# nRF52833_MCU.net
KiCad netlist of a schematic drawn in EAGLE
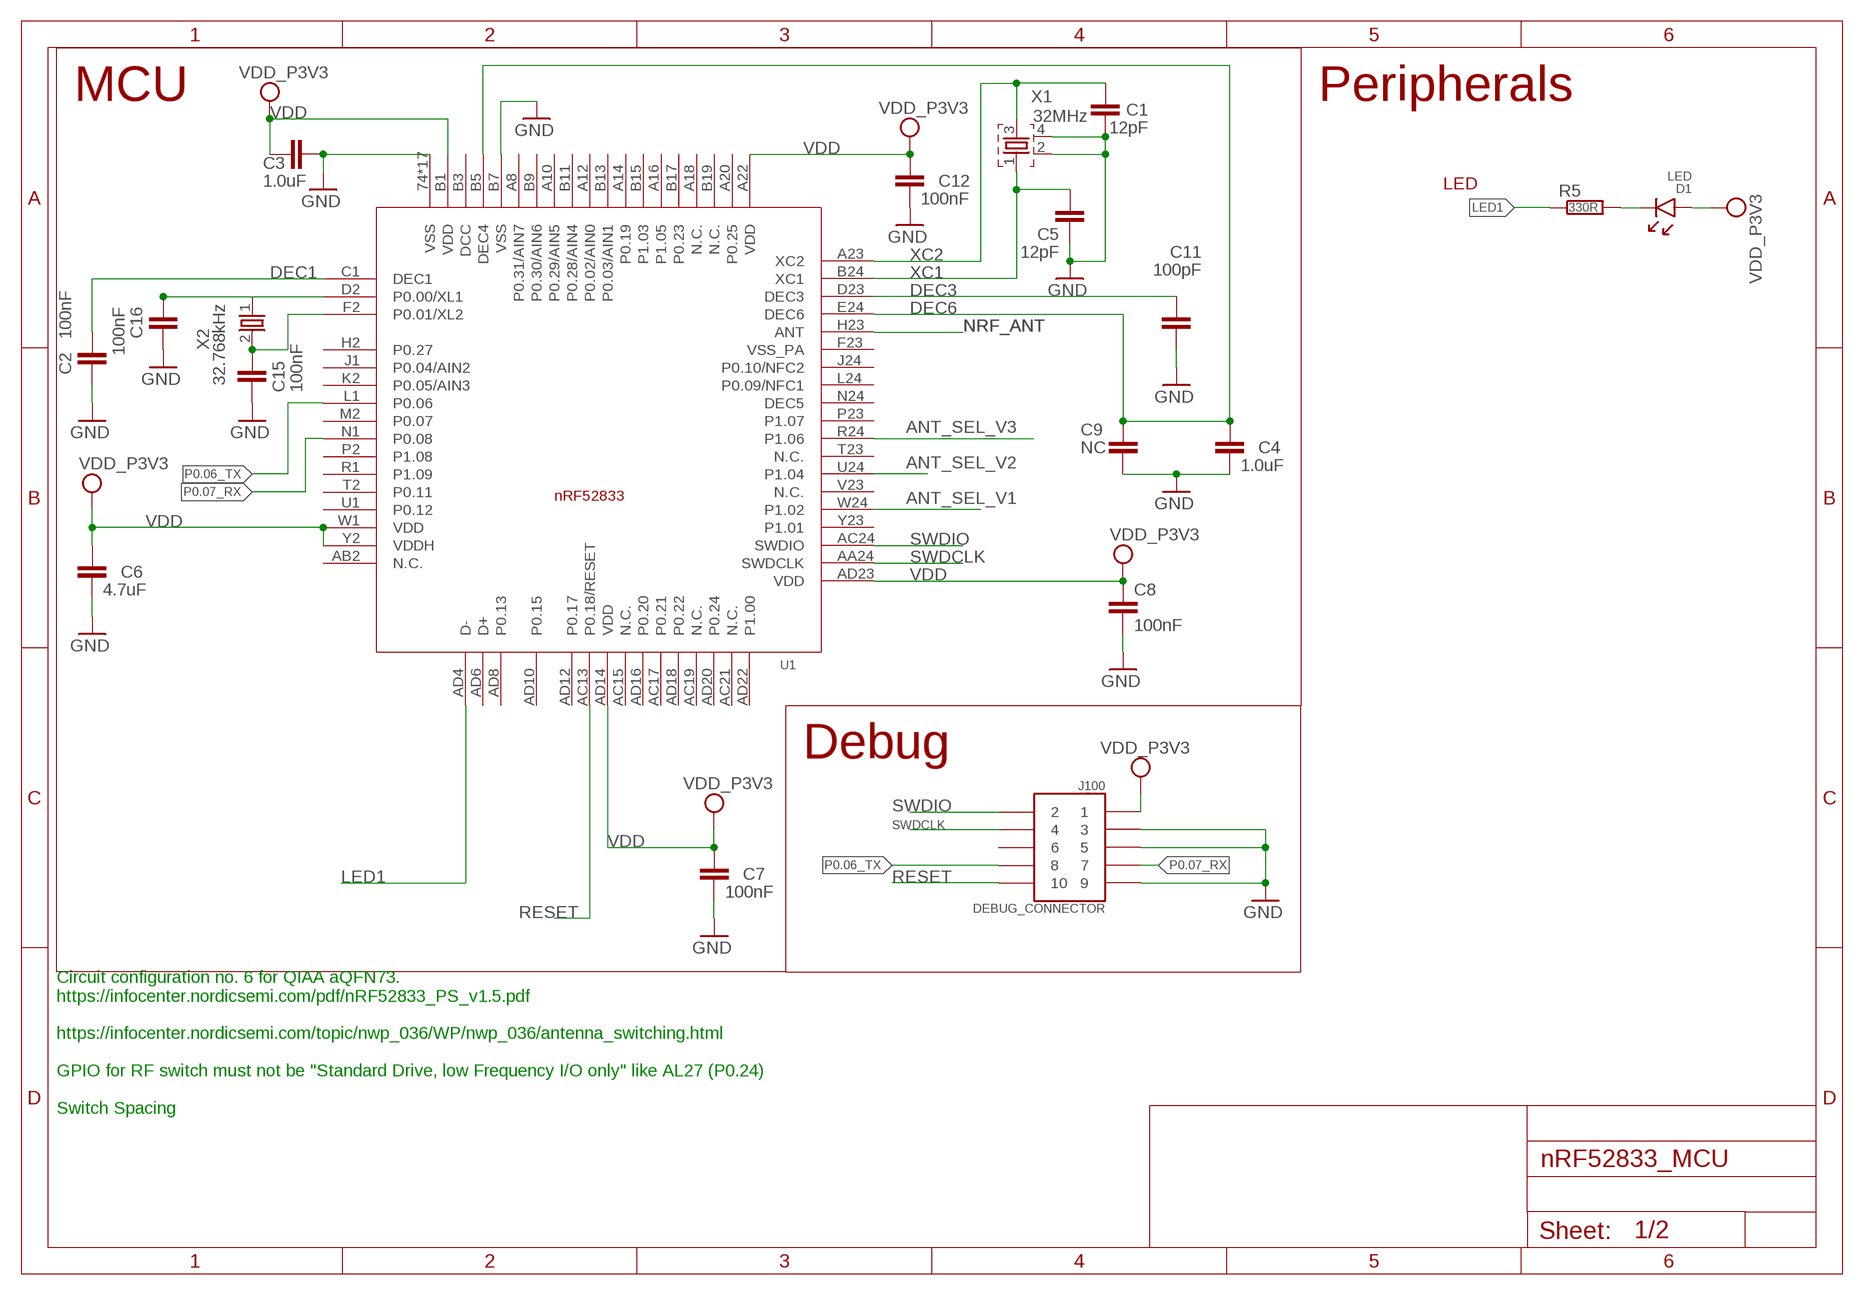
[diagram p0: schematic, sheet 1]
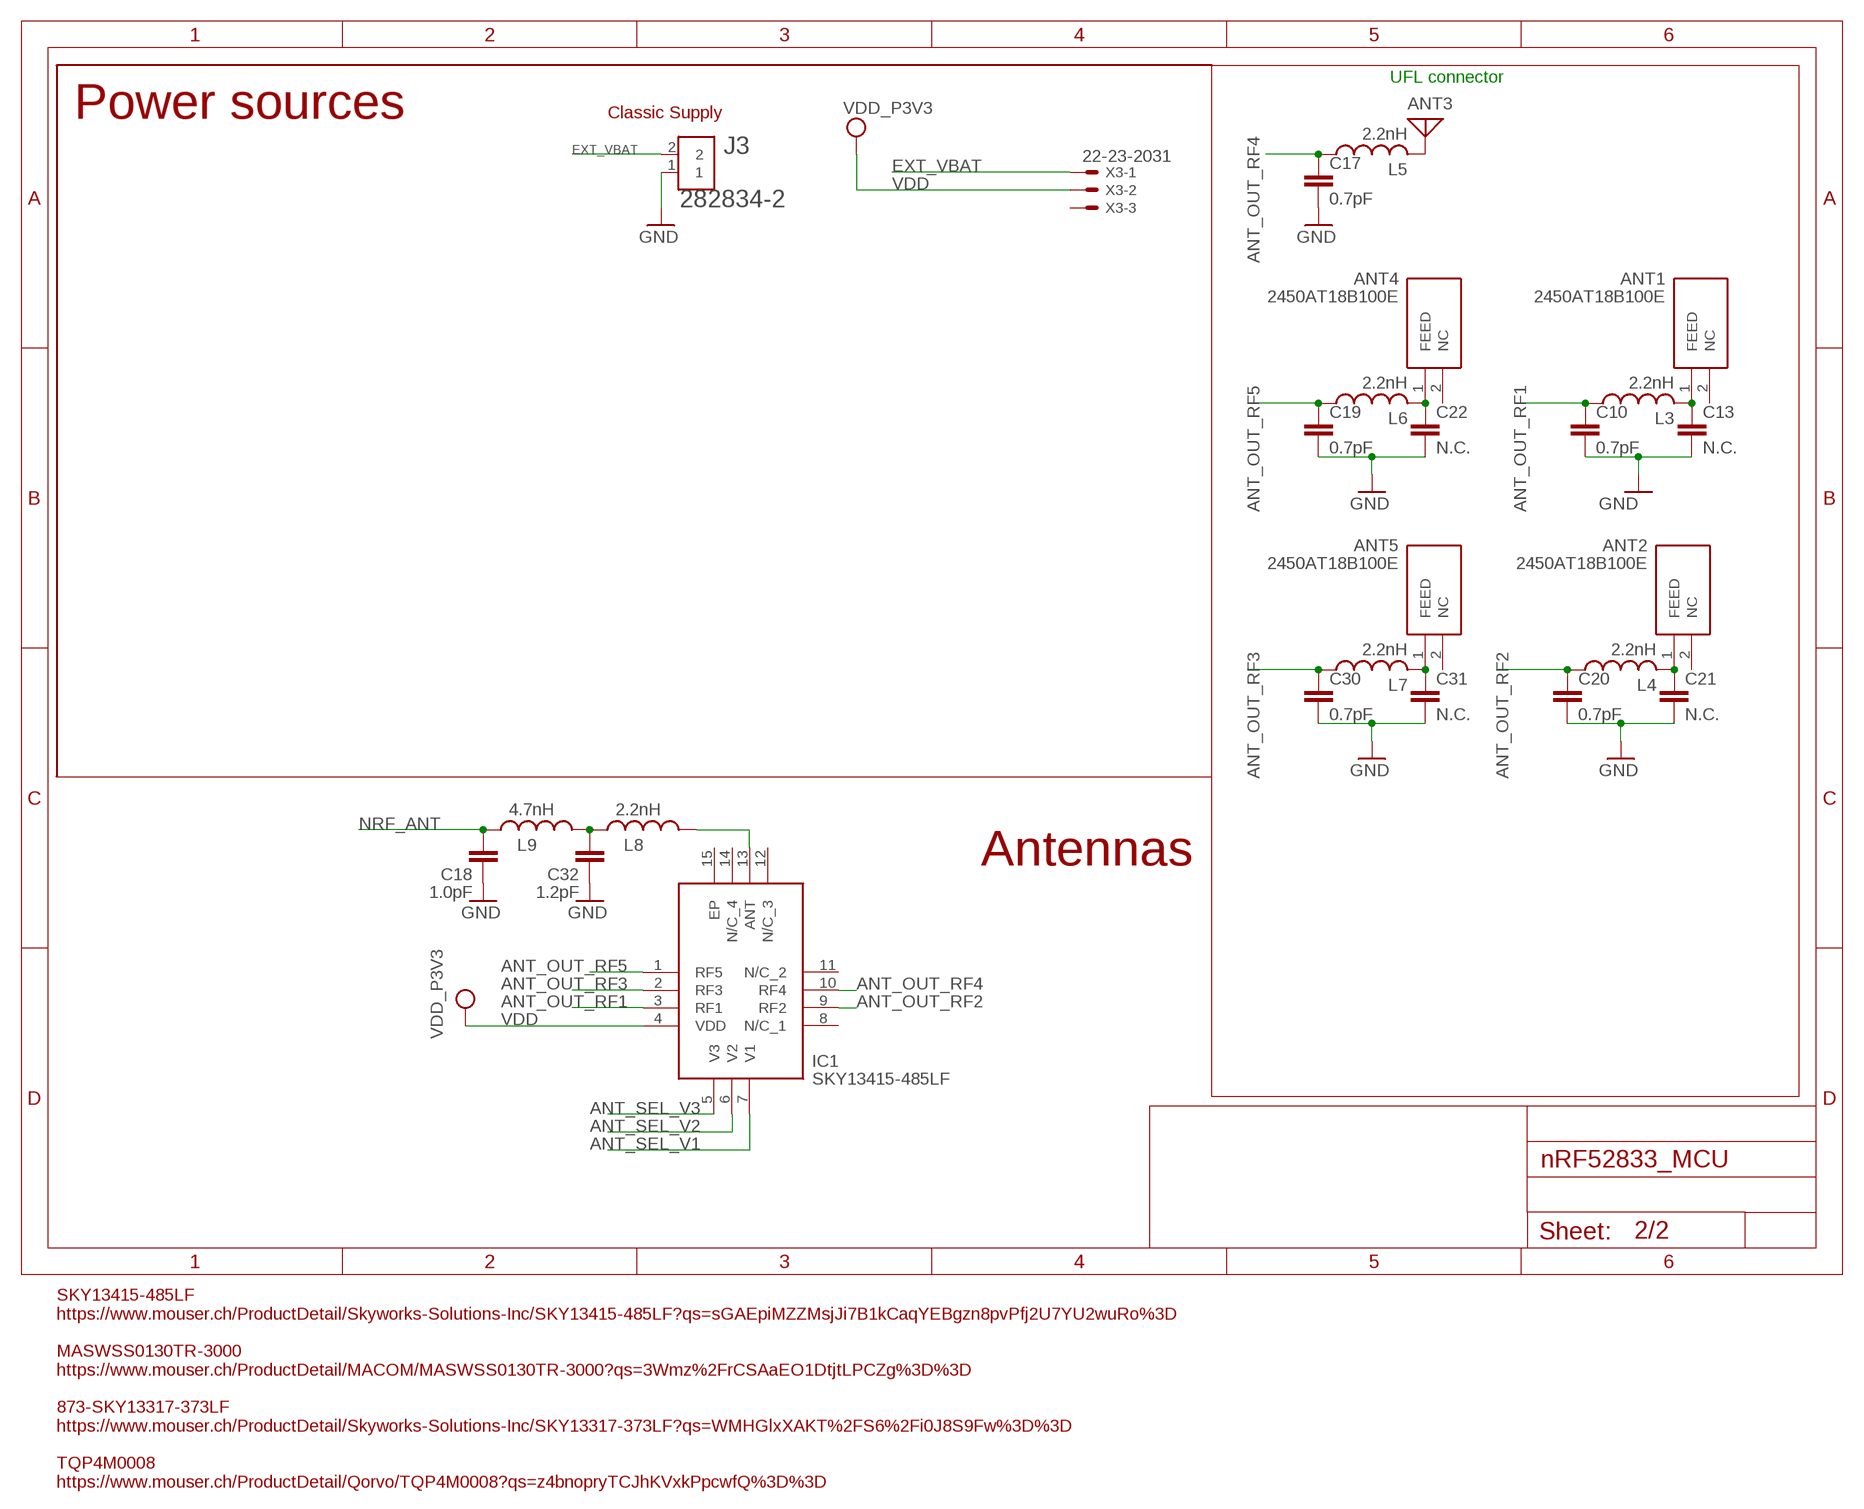
[diagram p1: schematic, sheet 2]

(export (version "E")
  (design (tool "Eeschema 10.0.6"))
  (components
    (comp (ref "ANT1")
      (value "2450AT18B100E")
      (footprint "eagle-import:ANTC3216X140N")
      (fields (field (name "MOUSER_PART_NUMBER") "609-2450AT18B100E"))
      (libsource (lib "eagle-import") (part "2450AT18B100E"))
    )
    (comp (ref "ANT2")
      (value "2450AT18B100E")
      (footprint "eagle-import:ANTC3216X140N")
      (fields (field (name "MOUSER_PART_NUMBER") "609-2450AT18B100E"))
      (libsource (lib "eagle-import") (part "2450AT18B100E"))
    )
    (comp (ref "ANT3")
      (value "ANTENNA")
      (footprint "eagle-import:PAD-01")
      (libsource (lib "eagle-import") (part "ANTENNA"))
    )
    (comp (ref "ANT4")
      (value "2450AT18B100E")
      (footprint "eagle-import:ANTC3216X140N")
      (fields (field (name "MOUSER_PART_NUMBER") "609-2450AT18B100E"))
      (libsource (lib "eagle-import") (part "2450AT18B100E"))
    )
    (comp (ref "ANT5")
      (value "2450AT18B100E")
      (footprint "eagle-import:ANTC3216X140N")
      (fields (field (name "MOUSER_PART_NUMBER") "609-2450AT18B100E"))
      (libsource (lib "eagle-import") (part "2450AT18B100E"))
    )
    (comp (ref "C10")
      (value "0.7pF")
      (footprint "eagle-import:RESC0402_N")
      (libsource (lib "eagle-import") (part "CAPACITOR_0402_N"))
    )
    (comp (ref "C13")
      (value "N.C.")
      (footprint "eagle-import:RESC0402_N")
      (libsource (lib "eagle-import") (part "CAPACITOR_0402_N"))
    )
    (comp (ref "C17")
      (value "0.7pF")
      (footprint "eagle-import:RESC0402_N")
      (libsource (lib "eagle-import") (part "CAPACITOR_0402_N"))
    )
    (comp (ref "C18")
      (value "1.0pF")
      (footprint "eagle-import:RESC0402_N")
      (libsource (lib "eagle-import") (part "CAPACITOR_0402_N"))
    )
    (comp (ref "C19")
      (value "0.7pF")
      (footprint "eagle-import:RESC0402_N")
      (libsource (lib "eagle-import") (part "CAPACITOR_0402_N"))
    )
    (comp (ref "C20")
      (value "0.7pF")
      (footprint "eagle-import:RESC0402_N")
      (libsource (lib "eagle-import") (part "CAPACITOR_0402_N"))
    )
    (comp (ref "C21")
      (value "N.C.")
      (footprint "eagle-import:RESC0402_N")
      (libsource (lib "eagle-import") (part "CAPACITOR_0402_N"))
    )
    (comp (ref "C22")
      (value "N.C.")
      (footprint "eagle-import:RESC0402_N")
      (libsource (lib "eagle-import") (part "CAPACITOR_0402_N"))
    )
    (comp (ref "C30")
      (value "0.7pF")
      (footprint "eagle-import:RESC0402_N")
      (libsource (lib "eagle-import") (part "CAPACITOR_0402_N"))
    )
    (comp (ref "C31")
      (value "N.C.")
      (footprint "eagle-import:RESC0402_N")
      (libsource (lib "eagle-import") (part "CAPACITOR_0402_N"))
    )
    (comp (ref "C32")
      (value "1.2pF")
      (footprint "eagle-import:RESC0402_N")
      (libsource (lib "eagle-import") (part "CAPACITOR_0402_N"))
    )
    (comp (ref "IC1")
      (value "SKY13415-485LF")
      (footprint "eagle-import:SKY13415485LF")
      (fields (field (name "MOUSER_PART_NUMBER") "873-SKY13415-485LF"))
      (libsource (lib "eagle-import") (part "SKY13415-485LF"))
    )
    (comp (ref "J3")
      (value "282834-2")
      (footprint "eagle-import:CONN_282834-2")
      (fields (field (name "MF") "TE Connectivity"))
      (libsource (lib "eagle-import") (part "282834-2"))
    )
    (comp (ref "L3")
      (value "2.2nH")
      (footprint "eagle-import:RESC0402_N")
      (libsource (lib "eagle-import") (part "INDUCTOR_0402_N"))
    )
    (comp (ref "L4")
      (value "2.2nH")
      (footprint "eagle-import:RESC0402_N")
      (libsource (lib "eagle-import") (part "INDUCTOR_0402_N"))
    )
    (comp (ref "L5")
      (value "2.2nH")
      (footprint "eagle-import:RESC0402_N")
      (libsource (lib "eagle-import") (part "INDUCTOR_0402_N"))
    )
    (comp (ref "L6")
      (value "2.2nH")
      (footprint "eagle-import:RESC0402_N")
      (libsource (lib "eagle-import") (part "INDUCTOR_0402_N"))
    )
    (comp (ref "L7")
      (value "2.2nH")
      (footprint "eagle-import:RESC0402_N")
      (libsource (lib "eagle-import") (part "INDUCTOR_0402_N"))
    )
    (comp (ref "L8")
      (value "2.2nH")
      (footprint "eagle-import:RESC0402_N")
      (libsource (lib "eagle-import") (part "INDUCTOR_0402_N"))
    )
    (comp (ref "L9")
      (value "4.7nH")
      (footprint "eagle-import:RESC0402_N")
      (libsource (lib "eagle-import") (part "INDUCTOR_0402_N"))
    )
    (comp (ref "X3")
      (value "22-23-2031")
      (footprint "eagle-import:22-23-2031")
      (fields (field (name "MF") "MOLEX"))
      (libsource (lib "eagle-import") (part "22-23-2031"))
    )
    (comp (ref "C1")
      (value "12pF")
      (footprint "eagle-import:RESC0402_N")
      (libsource (lib "eagle-import") (part "CAPACITOR_0402_N"))
    )
    (comp (ref "C2")
      (value "100nF")
      (footprint "eagle-import:RESC0402_N")
      (libsource (lib "eagle-import") (part "CAPACITOR_0402_N"))
    )
    (comp (ref "C3")
      (value "1.0uF")
      (footprint "eagle-import:RESC0402_N")
      (libsource (lib "eagle-import") (part "CAPACITOR_0402_N"))
    )
    (comp (ref "C4")
      (value "1.0uF")
      (footprint "eagle-import:RESC0402_N")
      (libsource (lib "eagle-import") (part "CAPACITOR_0402_N"))
    )
    (comp (ref "C5")
      (value "12pF")
      (footprint "eagle-import:RESC0402_N")
      (libsource (lib "eagle-import") (part "CAPACITOR_0402_N"))
    )
    (comp (ref "C6")
      (value "4.7uF")
      (footprint "eagle-import:RESC0402_N")
      (libsource (lib "eagle-import") (part "CAPACITOR_0402_N"))
    )
    (comp (ref "C7")
      (value "100nF")
      (footprint "eagle-import:RESC0402_N")
      (libsource (lib "eagle-import") (part "CAPACITOR_0402_N"))
    )
    (comp (ref "C8")
      (value "100nF")
      (footprint "eagle-import:RESC0402_N")
      (libsource (lib "eagle-import") (part "CAPACITOR_0402_N"))
    )
    (comp (ref "C9")
      (value "NC")
      (footprint "eagle-import:RESC0402_N")
      (libsource (lib "eagle-import") (part "CAPACITOR_0402_N"))
    )
    (comp (ref "C11")
      (value "100pF")
      (footprint "eagle-import:RESC0402_N")
      (libsource (lib "eagle-import") (part "CAPACITOR_0402_N"))
    )
    (comp (ref "C12")
      (value "100nF")
      (footprint "eagle-import:RESC0402_N")
      (libsource (lib "eagle-import") (part "CAPACITOR_0402_N"))
    )
    (comp (ref "C15")
      (value "100nF")
      (footprint "eagle-import:RESC0402_N")
      (libsource (lib "eagle-import") (part "CAPACITOR_0402_N"))
    )
    (comp (ref "C16")
      (value "100nF")
      (footprint "eagle-import:RESC0402_N")
      (libsource (lib "eagle-import") (part "CAPACITOR_0402_N"))
    )
    (comp (ref "D1")
      (value "LED")
      (footprint "eagle-import:DIOC0603_N")
      (libsource (lib "eagle-import") (part "LED"))
    )
    (comp (ref "J100")
      (value "DEBUG_CONNECTOR")
      (footprint "eagle-import:HDRV127P5X2-10_N")
      (libsource (lib "eagle-import") (part "DEBUG_CONNECTOR"))
    )
    (comp (ref "R5")
      (value "330R")
      (footprint "eagle-import:RESC0402_N")
      (libsource (lib "eagle-import") (part "RESISTOR_0402_N"))
    )
    (comp (ref "U1")
      (value "nRF52833-QIAA")
      (footprint "eagle-import:AQFN50P700X700X85_HS-74N")
      (fields
        (field (name "MANUFACTURER") "Nordic Semiconductor")
        (field (name "PUBLISHER") "Nordic Semiconductor")
      )
      (libsource (lib "eagle-import") (part "NRF52833_QIAANRF52833_QIAA_AQFN50P700X700X85_HS-74N"))
    )
    (comp (ref "X1")
      (value "32MHz")
      (footprint "eagle-import:BT-XTAL_2016_N")
      (libsource (lib "eagle-import") (part "XTAL_32MHZ"))
    )
    (comp (ref "X2")
      (value "32.768kHz")
      (footprint "eagle-import:XTAL_3215_N")
      (libsource (lib "eagle-import") (part "XTAL_32KHZ"))
    )
  )
  (nets
    (net (code "1") (name "ANT_OUT_RF1") (class "Default")
      (node (ref "C10") (pin "1") (pinfunction "1_1") (pintype "passive"))
      (node (ref "IC1") (pin "3") (pinfunction "RF1_3") (pintype "bidirectional"))
      (node (ref "L3") (pin "1") (pinfunction "1_1") (pintype "passive"))
    )
    (net (code "2") (name "ANT_OUT_RF2") (class "Default")
      (node (ref "C20") (pin "1") (pinfunction "1_1") (pintype "passive"))
      (node (ref "IC1") (pin "9") (pinfunction "RF2_9") (pintype "bidirectional"))
      (node (ref "L4") (pin "1") (pinfunction "1_1") (pintype "passive"))
    )
    (net (code "3") (name "ANT_OUT_RF3") (class "Default")
      (node (ref "C30") (pin "1") (pinfunction "1_1") (pintype "passive"))
      (node (ref "IC1") (pin "2") (pinfunction "RF3_2") (pintype "bidirectional"))
      (node (ref "L7") (pin "1") (pinfunction "1_1") (pintype "passive"))
    )
    (net (code "4") (name "ANT_OUT_RF4") (class "Default")
      (node (ref "C17") (pin "1") (pinfunction "1_1") (pintype "passive"))
      (node (ref "IC1") (pin "10") (pinfunction "RF4_10") (pintype "bidirectional"))
      (node (ref "L5") (pin "1") (pinfunction "1_1") (pintype "passive"))
    )
    (net (code "5") (name "ANT_OUT_RF5") (class "Default")
      (node (ref "C19") (pin "1") (pinfunction "1_1") (pintype "passive"))
      (node (ref "IC1") (pin "1") (pinfunction "RF5_1") (pintype "bidirectional"))
      (node (ref "L6") (pin "1") (pinfunction "1_1") (pintype "passive"))
    )
    (net (code "6") (name "ANT_SEL_V1") (class "Default")
      (node (ref "IC1") (pin "7") (pinfunction "V1_7") (pintype "bidirectional"))
      (node (ref "U1") (pin "W24") (pinfunction "P1.02_W24") (pintype "bidirectional"))
    )
    (net (code "7") (name "ANT_SEL_V2") (class "Default")
      (node (ref "IC1") (pin "6") (pinfunction "V2_6") (pintype "bidirectional"))
      (node (ref "U1") (pin "U24") (pinfunction "P1.04_U24") (pintype "bidirectional"))
    )
    (net (code "8") (name "ANT_SEL_V3") (class "Default")
      (node (ref "IC1") (pin "5") (pinfunction "V3_5") (pintype "bidirectional"))
      (node (ref "U1") (pin "R24") (pinfunction "P1.06_R24") (pintype "bidirectional"))
    )
    (net (code "9") (name "DEC1") (class "Default")
      (node (ref "C2") (pin "1") (pinfunction "1_1") (pintype "passive"))
      (node (ref "U1") (pin "C1") (pinfunction "DEC1_C1") (pintype "power_in"))
    )
    (net (code "10") (name "DEC3") (class "Default")
      (node (ref "C11") (pin "1") (pinfunction "1_1") (pintype "passive"))
      (node (ref "U1") (pin "D23") (pinfunction "DEC3_D23") (pintype "power_in"))
    )
    (net (code "11") (name "DEC5") (class "Default")
      (node (ref "U1") (pin "N24") (pinfunction "DEC5_N24") (pintype "power_in"))
    )
    (net (code "12") (name "DEC6") (class "Default")
      (node (ref "C4") (pin "1") (pinfunction "1_1") (pintype "passive"))
      (node (ref "C9") (pin "1") (pinfunction "1_1") (pintype "passive"))
      (node (ref "U1") (pin "B5") (pinfunction "DEC4_B5") (pintype "power_in"))
      (node (ref "U1") (pin "E24") (pinfunction "DEC6_E24") (pintype "power_in"))
    )
    (net (code "13") (name "EXT_VBAT") (class "Default")
      (node (ref "J3") (pin "2") (pinfunction "2_2") (pintype "passive"))
      (node (ref "X3") (pin "1") (pinfunction "S_1") (pintype "passive"))
    )
    (net (code "14") (name "GND") (class "Default")
      (node (ref "C1") (pin "2") (pinfunction "2_2") (pintype "passive"))
      (node (ref "C10") (pin "2") (pinfunction "2_2") (pintype "passive"))
      (node (ref "C11") (pin "2") (pinfunction "2_2") (pintype "passive"))
      (node (ref "C12") (pin "2") (pinfunction "2_2") (pintype "passive"))
      (node (ref "C13") (pin "2") (pinfunction "2_2") (pintype "passive"))
      (node (ref "C15") (pin "1") (pinfunction "1_1") (pintype "passive"))
      (node (ref "C16") (pin "1") (pinfunction "1_1") (pintype "passive"))
      (node (ref "C17") (pin "2") (pinfunction "2_2") (pintype "passive"))
      (node (ref "C18") (pin "2") (pinfunction "2_2") (pintype "passive"))
      (node (ref "C19") (pin "2") (pinfunction "2_2") (pintype "passive"))
      (node (ref "C2") (pin "2") (pinfunction "2_2") (pintype "passive"))
      (node (ref "C20") (pin "2") (pinfunction "2_2") (pintype "passive"))
      (node (ref "C21") (pin "2") (pinfunction "2_2") (pintype "passive"))
      (node (ref "C22") (pin "2") (pinfunction "2_2") (pintype "passive"))
      (node (ref "C3") (pin "2") (pinfunction "2_2") (pintype "passive"))
      (node (ref "C30") (pin "2") (pinfunction "2_2") (pintype "passive"))
      (node (ref "C31") (pin "2") (pinfunction "2_2") (pintype "passive"))
      (node (ref "C32") (pin "2") (pinfunction "2_2") (pintype "passive"))
      (node (ref "C4") (pin "2") (pinfunction "2_2") (pintype "passive"))
      (node (ref "C5") (pin "2") (pinfunction "2_2") (pintype "passive"))
      (node (ref "C6") (pin "2") (pinfunction "2_2") (pintype "passive"))
      (node (ref "C7") (pin "2") (pinfunction "2_2") (pintype "passive"))
      (node (ref "C8") (pin "2") (pinfunction "2_2") (pintype "passive"))
      (node (ref "C9") (pin "2") (pinfunction "2_2") (pintype "passive"))
      (node (ref "J100") (pin "3") (pinfunction "3_3") (pintype "bidirectional"))
      (node (ref "J100") (pin "5") (pinfunction "5_5") (pintype "bidirectional"))
      (node (ref "J100") (pin "9") (pinfunction "9_9") (pintype "bidirectional"))
      (node (ref "J3") (pin "1") (pinfunction "1_1") (pintype "passive"))
      (node (ref "U1") (pin "74") (pinfunction "VSS_74") (pintype "power_in"))
      (node (ref "U1") (pin "B7") (pinfunction "VSS_B7") (pintype "power_in"))
      (node (ref "U1") (pin "P$1") (pinfunction "VSS_P$1") (pintype "power_in"))
      (node (ref "U1") (pin "P$10") (pinfunction "VSS_P$10") (pintype "power_in"))
      (node (ref "U1") (pin "P$11") (pinfunction "VSS_P$11") (pintype "power_in"))
      (node (ref "U1") (pin "P$12") (pinfunction "VSS_P$12") (pintype "power_in"))
      (node (ref "U1") (pin "P$13") (pinfunction "VSS_P$13") (pintype "power_in"))
      (node (ref "U1") (pin "P$14") (pinfunction "VSS_P$14") (pintype "power_in"))
      (node (ref "U1") (pin "P$15") (pinfunction "VSS_P$15") (pintype "power_in"))
      (node (ref "U1") (pin "P$16") (pinfunction "VSS_P$16") (pintype "power_in"))
      (node (ref "U1") (pin "P$17") (pinfunction "VSS_P$17") (pintype "power_in"))
      (node (ref "U1") (pin "P$18") (pinfunction "VSS_P$18") (pintype "power_in"))
      (node (ref "U1") (pin "P$19") (pinfunction "VSS_P$19") (pintype "power_in"))
      (node (ref "U1") (pin "P$2") (pinfunction "VSS_P$2") (pintype "power_in"))
      (node (ref "U1") (pin "P$20") (pinfunction "VSS_P$20") (pintype "power_in"))
      (node (ref "U1") (pin "P$3") (pinfunction "VSS_P$3") (pintype "power_in"))
      (node (ref "U1") (pin "P$4") (pinfunction "VSS_P$4") (pintype "power_in"))
      (node (ref "U1") (pin "P$5") (pinfunction "VSS_P$5") (pintype "power_in"))
      (node (ref "X1") (pin "2") (pinfunction "2_2") (pintype "passive"))
      (node (ref "X1") (pin "4") (pinfunction "4_4") (pintype "passive"))
    )
    (net (code "15") (name "LED1") (class "Default")
      (node (ref "R5") (pin "1") (pinfunction "1_1") (pintype "passive"))
      (node (ref "U1") (pin "AD4") (pinfunction "D-_AD4") (pintype "bidirectional"))
    )
    (net (code "16") (name "NRF_ANT") (class "Default")
      (node (ref "C18") (pin "1") (pinfunction "1_1") (pintype "passive"))
      (node (ref "L9") (pin "1") (pinfunction "1_1") (pintype "passive"))
      (node (ref "U1") (pin "H23") (pinfunction "ANT_H23") (pintype "bidirectional"))
    )
    (net (code "17") (name "Net-(ANT1-FEED)") (class "Default")
      (node (ref "ANT1") (pin "1") (pinfunction "FEED_1") (pintype "input"))
      (node (ref "C13") (pin "1") (pinfunction "1_1") (pintype "passive"))
      (node (ref "L3") (pin "2") (pinfunction "2_2") (pintype "passive"))
    )
    (net (code "18") (name "Net-(ANT2-FEED)") (class "Default")
      (node (ref "ANT2") (pin "1") (pinfunction "FEED_1") (pintype "input"))
      (node (ref "C21") (pin "1") (pinfunction "1_1") (pintype "passive"))
      (node (ref "L4") (pin "2") (pinfunction "2_2") (pintype "passive"))
    )
    (net (code "19") (name "Net-(ANT3-Pad1)") (class "Default")
      (node (ref "ANT3") (pin "1") (pinfunction "1_1") (pintype "output"))
      (node (ref "L5") (pin "2") (pinfunction "2_2") (pintype "passive"))
    )
    (net (code "20") (name "Net-(ANT4-FEED)") (class "Default")
      (node (ref "ANT4") (pin "1") (pinfunction "FEED_1") (pintype "input"))
      (node (ref "C22") (pin "1") (pinfunction "1_1") (pintype "passive"))
      (node (ref "L6") (pin "2") (pinfunction "2_2") (pintype "passive"))
    )
    (net (code "21") (name "Net-(ANT5-FEED)") (class "Default")
      (node (ref "ANT5") (pin "1") (pinfunction "FEED_1") (pintype "input"))
      (node (ref "C31") (pin "1") (pinfunction "1_1") (pintype "passive"))
      (node (ref "L7") (pin "2") (pinfunction "2_2") (pintype "passive"))
    )
    (net (code "22") (name "Net-(C32-Pad1)") (class "Default")
      (node (ref "C32") (pin "1") (pinfunction "1_1") (pintype "passive"))
      (node (ref "L8") (pin "1") (pinfunction "1_1") (pintype "passive"))
      (node (ref "L9") (pin "2") (pinfunction "2_2") (pintype "passive"))
    )
    (net (code "23") (name "Net-(D1-C)") (class "Default")
      (node (ref "D1") (pin "1") (pinfunction "C_1") (pintype "bidirectional"))
      (node (ref "R5") (pin "2") (pinfunction "2_2") (pintype "passive"))
    )
    (net (code "24") (name "Net-(IC1-ANT)") (class "Default")
      (node (ref "IC1") (pin "13") (pinfunction "ANT_13") (pintype "bidirectional"))
      (node (ref "L8") (pin "2") (pinfunction "2_2") (pintype "passive"))
    )
    (net (code "25") (name "Net-(U1-P0.00{slash}XL1)") (class "Default")
      (node (ref "C16") (pin "2") (pinfunction "2_2") (pintype "passive"))
      (node (ref "U1") (pin "D2") (pinfunction "P0.00/XL1_D2") (pintype "bidirectional"))
      (node (ref "X2") (pin "1") (pinfunction "1_1") (pintype "passive"))
    )
    (net (code "26") (name "Net-(U1-P0.01{slash}XL2)") (class "Default")
      (node (ref "C15") (pin "2") (pinfunction "2_2") (pintype "passive"))
      (node (ref "U1") (pin "F2") (pinfunction "P0.01/XL2_F2") (pintype "bidirectional"))
      (node (ref "X2") (pin "2") (pinfunction "2_2") (pintype "passive"))
    )
    (net (code "27") (name "P0.06_TX") (class "Default")
      (node (ref "J100") (pin "8") (pinfunction "8_8") (pintype "bidirectional"))
      (node (ref "U1") (pin "L1") (pinfunction "P0.06_L1") (pintype "bidirectional"))
    )
    (net (code "28") (name "P0.07_RX") (class "Default")
      (node (ref "J100") (pin "7") (pinfunction "7_7") (pintype "bidirectional"))
      (node (ref "U1") (pin "N1") (pinfunction "P0.08_N1") (pintype "bidirectional"))
    )
    (net (code "29") (name "RESET") (class "Default")
      (node (ref "J100") (pin "10") (pinfunction "10_10") (pintype "bidirectional"))
      (node (ref "U1") (pin "AC13") (pinfunction "P0.18/RESET_AC13") (pintype "bidirectional"))
    )
    (net (code "30") (name "SWDCLK") (class "Default")
      (node (ref "J100") (pin "4") (pinfunction "4_4") (pintype "bidirectional"))
      (node (ref "U1") (pin "AA24") (pinfunction "SWDCLK_AA24") (pintype "input"))
    )
    (net (code "31") (name "SWDIO") (class "Default")
      (node (ref "J100") (pin "2") (pinfunction "2_2") (pintype "bidirectional"))
      (node (ref "U1") (pin "AC24") (pinfunction "SWDIO_AC24") (pintype "bidirectional"))
    )
    (net (code "32") (name "VDD") (class "Default")
      (node (ref "C12") (pin "1") (pinfunction "1_1") (pintype "passive"))
      (node (ref "C3") (pin "1") (pinfunction "1_1") (pintype "passive"))
      (node (ref "C6") (pin "1") (pinfunction "1_1") (pintype "passive"))
      (node (ref "C7") (pin "1") (pinfunction "1_1") (pintype "passive"))
      (node (ref "C8") (pin "1") (pinfunction "1_1") (pintype "passive"))
      (node (ref "D1") (pin "2") (pinfunction "A_2") (pintype "bidirectional"))
      (node (ref "IC1") (pin "4") (pinfunction "VDD_4") (pintype "bidirectional"))
      (node (ref "J100") (pin "1") (pinfunction "1_1") (pintype "bidirectional"))
      (node (ref "U1") (pin "A22") (pinfunction "VDD_A22") (pintype "power_in"))
      (node (ref "U1") (pin "AD14") (pinfunction "VDD_AD14") (pintype "power_in"))
      (node (ref "U1") (pin "AD23") (pinfunction "VDD_AD23") (pintype "power_in"))
      (node (ref "U1") (pin "B1") (pinfunction "VDD_B1") (pintype "power_in"))
      (node (ref "U1") (pin "W1") (pinfunction "VDD_W1") (pintype "power_in"))
      (node (ref "U1") (pin "Y2") (pinfunction "VDDH_Y2") (pintype "power_in"))
      (node (ref "X3") (pin "2") (pinfunction "S_2") (pintype "passive"))
    )
    (net (code "33") (name "VSS_PA") (class "Default")
      (node (ref "U1") (pin "F23") (pinfunction "VSS_PA_F23") (pintype "power_in"))
    )
    (net (code "34") (name "XC1") (class "Default")
      (node (ref "C5") (pin "1") (pinfunction "1_1") (pintype "passive"))
      (node (ref "U1") (pin "B24") (pinfunction "XC1_B24") (pintype "input"))
      (node (ref "X1") (pin "1") (pinfunction "1_1") (pintype "passive"))
    )
    (net (code "35") (name "XC2") (class "Default")
      (node (ref "C1") (pin "1") (pinfunction "1_1") (pintype "passive"))
      (node (ref "U1") (pin "A23") (pinfunction "XC2_A23") (pintype "output"))
      (node (ref "X1") (pin "3") (pinfunction "3_3") (pintype "passive"))
    )
    (net (code "36") (name "unconnected-(ANT1-NC-Pad2)") (class "Default")
      (node (ref "ANT1") (pin "2") (pinfunction "NC_2") (pintype "no_connect"))
    )
    (net (code "37") (name "unconnected-(ANT2-NC-Pad2)") (class "Default")
      (node (ref "ANT2") (pin "2") (pinfunction "NC_2") (pintype "no_connect"))
    )
    (net (code "38") (name "unconnected-(ANT4-NC-Pad2)") (class "Default")
      (node (ref "ANT4") (pin "2") (pinfunction "NC_2") (pintype "no_connect"))
    )
    (net (code "39") (name "unconnected-(ANT5-NC-Pad2)") (class "Default")
      (node (ref "ANT5") (pin "2") (pinfunction "NC_2") (pintype "no_connect"))
    )
    (net (code "40") (name "unconnected-(IC1-EP-Pad15)") (class "Default")
      (node (ref "IC1") (pin "15") (pinfunction "EP_15") (pintype "bidirectional"))
    )
    (net (code "41") (name "unconnected-(IC1-N{slash}C_1-Pad8)") (class "Default")
      (node (ref "IC1") (pin "8") (pinfunction "N/C_1_8") (pintype "bidirectional"))
    )
    (net (code "42") (name "unconnected-(IC1-N{slash}C_2-Pad11)") (class "Default")
      (node (ref "IC1") (pin "11") (pinfunction "N/C_2_11") (pintype "bidirectional"))
    )
    (net (code "43") (name "unconnected-(IC1-N{slash}C_3-Pad12)") (class "Default")
      (node (ref "IC1") (pin "12") (pinfunction "N/C_3_12") (pintype "bidirectional"))
    )
    (net (code "44") (name "unconnected-(IC1-N{slash}C_4-Pad14)") (class "Default")
      (node (ref "IC1") (pin "14") (pinfunction "N/C_4_14") (pintype "bidirectional"))
    )
    (net (code "45") (name "unconnected-(J100-Pad6)") (class "Default")
      (node (ref "J100") (pin "6") (pinfunction "6_6") (pintype "bidirectional"))
    )
    (net (code "46") (name "unconnected-(U1-D+-PadAD6)") (class "Default")
      (node (ref "U1") (pin "AD6") (pinfunction "D+_AD6") (pintype "bidirectional"))
    )
    (net (code "47") (name "unconnected-(U1-DCC-PadB3)") (class "Default")
      (node (ref "U1") (pin "B3") (pinfunction "DCC_B3") (pintype "output"))
    )
    (net (code "48") (name "unconnected-(U1-N.C.-PadA18)") (class "Default")
      (node (ref "U1") (pin "A18") (pinfunction "N.C._A18") (pintype "passive"))
    )
    (net (code "49") (name "unconnected-(U1-N.C.-PadAB2)") (class "Default")
      (node (ref "U1") (pin "AB2") (pinfunction "N.C._AB2") (pintype "passive"))
    )
    (net (code "50") (name "unconnected-(U1-N.C.-PadAC15)") (class "Default")
      (node (ref "U1") (pin "AC15") (pinfunction "N.C._AC15") (pintype "passive"))
    )
    (net (code "51") (name "unconnected-(U1-N.C.-PadAC19)") (class "Default")
      (node (ref "U1") (pin "AC19") (pinfunction "N.C._AC19") (pintype "passive"))
    )
    (net (code "52") (name "unconnected-(U1-N.C.-PadAC21)") (class "Default")
      (node (ref "U1") (pin "AC21") (pinfunction "N.C._AC21") (pintype "passive"))
    )
    (net (code "53") (name "unconnected-(U1-N.C.-PadB19)") (class "Default")
      (node (ref "U1") (pin "B19") (pinfunction "N.C._B19") (pintype "passive"))
    )
    (net (code "54") (name "unconnected-(U1-N.C.-PadT23)") (class "Default")
      (node (ref "U1") (pin "T23") (pinfunction "N.C._T23") (pintype "passive"))
    )
    (net (code "55") (name "unconnected-(U1-N.C.-PadV23)") (class "Default")
      (node (ref "U1") (pin "V23") (pinfunction "N.C._V23") (pintype "passive"))
    )
    (net (code "56") (name "unconnected-(U1-P0.02{slash}AIN0-PadA12)") (class "Default")
      (node (ref "U1") (pin "A12") (pinfunction "P0.02/AIN0_A12") (pintype "bidirectional"))
    )
    (net (code "57") (name "unconnected-(U1-P0.03{slash}AIN1-PadB13)") (class "Default")
      (node (ref "U1") (pin "B13") (pinfunction "P0.03/AIN1_B13") (pintype "bidirectional"))
    )
    (net (code "58") (name "unconnected-(U1-P0.04{slash}AIN2-PadJ1)") (class "Default")
      (node (ref "U1") (pin "J1") (pinfunction "P0.04/AIN2_J1") (pintype "bidirectional"))
    )
    (net (code "59") (name "unconnected-(U1-P0.05{slash}AIN3-PadK2)") (class "Default")
      (node (ref "U1") (pin "K2") (pinfunction "P0.05/AIN3_K2") (pintype "bidirectional"))
    )
    (net (code "60") (name "unconnected-(U1-P0.07-PadM2)") (class "Default")
      (node (ref "U1") (pin "M2") (pinfunction "P0.07_M2") (pintype "bidirectional"))
    )
    (net (code "61") (name "unconnected-(U1-P0.09{slash}NFC1-PadL24)") (class "Default")
      (node (ref "U1") (pin "L24") (pinfunction "P0.09/NFC1_L24") (pintype "bidirectional"))
    )
    (net (code "62") (name "unconnected-(U1-P0.10{slash}NFC2-PadJ24)") (class "Default")
      (node (ref "U1") (pin "J24") (pinfunction "P0.10/NFC2_J24") (pintype "bidirectional"))
    )
    (net (code "63") (name "unconnected-(U1-P0.11-PadT2)") (class "Default")
      (node (ref "U1") (pin "T2") (pinfunction "P0.11_T2") (pintype "bidirectional"))
    )
    (net (code "64") (name "unconnected-(U1-P0.12-PadU1)") (class "Default")
      (node (ref "U1") (pin "U1") (pinfunction "P0.12_U1") (pintype "bidirectional"))
    )
    (net (code "65") (name "unconnected-(U1-P0.13-PadAD8)") (class "Default")
      (node (ref "U1") (pin "AD8") (pinfunction "P0.13_AD8") (pintype "bidirectional"))
    )
    (net (code "66") (name "unconnected-(U1-P0.15-PadAD10)") (class "Default")
      (node (ref "U1") (pin "AD10") (pinfunction "P0.15_AD10") (pintype "bidirectional"))
    )
    (net (code "67") (name "unconnected-(U1-P0.17-PadAD12)") (class "Default")
      (node (ref "U1") (pin "AD12") (pinfunction "P0.17_AD12") (pintype "bidirectional"))
    )
    (net (code "68") (name "unconnected-(U1-P0.19-PadA14)") (class "Default")
      (node (ref "U1") (pin "A14") (pinfunction "P0.19_A14") (pintype "bidirectional"))
    )
    (net (code "69") (name "unconnected-(U1-P0.20-PadAD16)") (class "Default")
      (node (ref "U1") (pin "AD16") (pinfunction "P0.20_AD16") (pintype "bidirectional"))
    )
    (net (code "70") (name "unconnected-(U1-P0.21-PadAC17)") (class "Default")
      (node (ref "U1") (pin "AC17") (pinfunction "P0.21_AC17") (pintype "bidirectional"))
    )
    (net (code "71") (name "unconnected-(U1-P0.22-PadAD18)") (class "Default")
      (node (ref "U1") (pin "AD18") (pinfunction "P0.22_AD18") (pintype "bidirectional"))
    )
    (net (code "72") (name "unconnected-(U1-P0.23-PadB17)") (class "Default")
      (node (ref "U1") (pin "B17") (pinfunction "P0.23_B17") (pintype "bidirectional"))
    )
    (net (code "73") (name "unconnected-(U1-P0.24-PadAD20)") (class "Default")
      (node (ref "U1") (pin "AD20") (pinfunction "P0.24_AD20") (pintype "bidirectional"))
    )
    (net (code "74") (name "unconnected-(U1-P0.25-PadA20)") (class "Default")
      (node (ref "U1") (pin "A20") (pinfunction "P0.25_A20") (pintype "bidirectional"))
    )
    (net (code "75") (name "unconnected-(U1-P0.27-PadH2)") (class "Default")
      (node (ref "U1") (pin "H2") (pinfunction "P0.27_H2") (pintype "bidirectional"))
    )
    (net (code "76") (name "unconnected-(U1-P0.28{slash}AIN4-PadB11)") (class "Default")
      (node (ref "U1") (pin "B11") (pinfunction "P0.28/AIN4_B11") (pintype "bidirectional"))
    )
    (net (code "77") (name "unconnected-(U1-P0.29{slash}AIN5-PadA10)") (class "Default")
      (node (ref "U1") (pin "A10") (pinfunction "P0.29/AIN5_A10") (pintype "bidirectional"))
    )
    (net (code "78") (name "unconnected-(U1-P0.30{slash}AIN6-PadB9)") (class "Default")
      (node (ref "U1") (pin "B9") (pinfunction "P0.30/AIN6_B9") (pintype "bidirectional"))
    )
    (net (code "79") (name "unconnected-(U1-P0.31{slash}AIN7-PadA8)") (class "Default")
      (node (ref "U1") (pin "A8") (pinfunction "P0.31/AIN7_A8") (pintype "bidirectional"))
    )
    (net (code "80") (name "unconnected-(U1-P1.00-PadAD22)") (class "Default")
      (node (ref "U1") (pin "AD22") (pinfunction "P1.00_AD22") (pintype "bidirectional"))
    )
    (net (code "81") (name "unconnected-(U1-P1.01-PadY23)") (class "Default")
      (node (ref "U1") (pin "Y23") (pinfunction "P1.01_Y23") (pintype "bidirectional"))
    )
    (net (code "82") (name "unconnected-(U1-P1.03-PadB15)") (class "Default")
      (node (ref "U1") (pin "B15") (pinfunction "P1.03_B15") (pintype "bidirectional"))
    )
    (net (code "83") (name "unconnected-(U1-P1.05-PadA16)") (class "Default")
      (node (ref "U1") (pin "A16") (pinfunction "P1.05_A16") (pintype "bidirectional"))
    )
    (net (code "84") (name "unconnected-(U1-P1.07-PadP23)") (class "Default")
      (node (ref "U1") (pin "P23") (pinfunction "P1.07_P23") (pintype "bidirectional"))
    )
    (net (code "85") (name "unconnected-(U1-P1.08-PadP2)") (class "Default")
      (node (ref "U1") (pin "P2") (pinfunction "P1.08_P2") (pintype "bidirectional"))
    )
    (net (code "86") (name "unconnected-(U1-P1.09-PadR1)") (class "Default")
      (node (ref "U1") (pin "R1") (pinfunction "P1.09_R1") (pintype "bidirectional"))
    )
    (net (code "87") (name "unconnected-(X3C-S-Pad3)") (class "Default")
      (node (ref "X3") (pin "3") (pinfunction "S_3") (pintype "passive"))
    )
  )
)
